# adapter.net
KiCad netlist of a schematic drawn in EAGLE
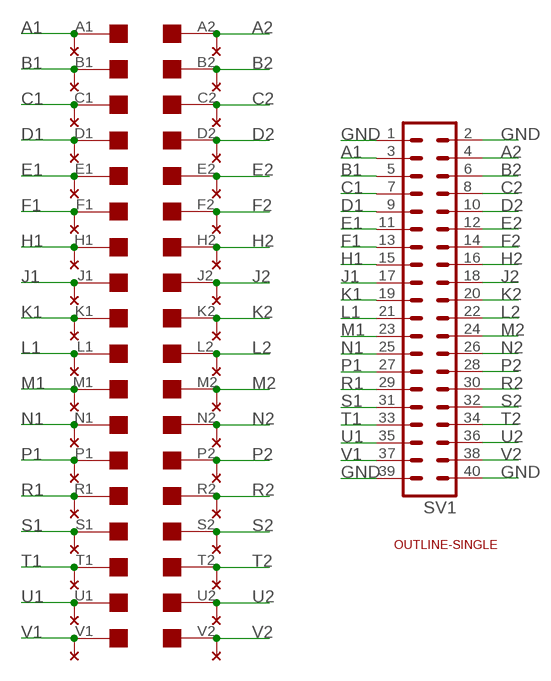
[diagram p0: schematic, sheet 1]

(export (version "E")
  (design (tool "Eeschema 10.0.6"))
  (components
    (comp (ref "EDGE1")
      (value "EDGE-2CONNECTOR")
      (footprint "eagle-import:EDGE-CON2")
      (libsource (lib "eagle-import") (part "EDGE-2CONNECTOR"))
    )
    (comp (ref "SV1")
      (value "MA20-2")
      (footprint "eagle-import:MA20-2")
      (libsource (lib "eagle-import") (part "MA20-2"))
    )
    (comp (ref "U$2")
      (value "OUTLINE-SINGLE")
      (footprint "eagle-import:SINGLE")
      (libsource (lib "eagle-import") (part "OUTLINE-SINGLE"))
    )
    (comp (ref "U$3")
      (value "THRU-HOLE2")
      (footprint "eagle-import:THRU-HOLEB")
      (libsource (lib "eagle-import") (part "THRU-HOLE2"))
    )
  )
  (nets
    (net (code "1") (name "/A1") (class "Default")
      (node (ref "EDGE1") (pin "A1") (pinfunction "1_A1") (pintype "bidirectional"))
      (node (ref "SV1") (pin "3") (pinfunction "3_3") (pintype "passive"))
      (node (ref "U$3") (pin "A1") (pinfunction "P$1_A1") (pintype "passive"))
    )
    (net (code "2") (name "/A2") (class "Default")
      (node (ref "EDGE1") (pin "A2") (pinfunction "1_A2") (pintype "bidirectional"))
      (node (ref "SV1") (pin "4") (pinfunction "4_4") (pintype "passive"))
      (node (ref "U$3") (pin "A2") (pinfunction "P$1_A2") (pintype "passive"))
    )
    (net (code "3") (name "/B1") (class "Default")
      (node (ref "EDGE1") (pin "B1") (pinfunction "1_B1") (pintype "bidirectional"))
      (node (ref "SV1") (pin "5") (pinfunction "5_5") (pintype "passive"))
      (node (ref "U$3") (pin "B1") (pinfunction "P$1_B1") (pintype "passive"))
    )
    (net (code "4") (name "/B2") (class "Default")
      (node (ref "EDGE1") (pin "B2") (pinfunction "1_B2") (pintype "bidirectional"))
      (node (ref "SV1") (pin "6") (pinfunction "6_6") (pintype "passive"))
      (node (ref "U$3") (pin "B2") (pinfunction "P$1_B2") (pintype "passive"))
    )
    (net (code "5") (name "/C1") (class "Default")
      (node (ref "EDGE1") (pin "C1") (pinfunction "1_C1") (pintype "bidirectional"))
      (node (ref "SV1") (pin "7") (pinfunction "7_7") (pintype "passive"))
      (node (ref "U$3") (pin "C1") (pinfunction "P$1_C1") (pintype "passive"))
    )
    (net (code "6") (name "/C2") (class "Default")
      (node (ref "EDGE1") (pin "C2") (pinfunction "1_C2") (pintype "bidirectional"))
      (node (ref "SV1") (pin "8") (pinfunction "8_8") (pintype "passive"))
      (node (ref "U$3") (pin "C2") (pinfunction "P$1_C2") (pintype "passive"))
    )
    (net (code "7") (name "/D1") (class "Default")
      (node (ref "EDGE1") (pin "D1") (pinfunction "1_D1") (pintype "bidirectional"))
      (node (ref "SV1") (pin "9") (pinfunction "9_9") (pintype "passive"))
      (node (ref "U$3") (pin "D1") (pinfunction "P$1_D1") (pintype "passive"))
    )
    (net (code "8") (name "/D2") (class "Default")
      (node (ref "EDGE1") (pin "D2") (pinfunction "1_D2") (pintype "bidirectional"))
      (node (ref "SV1") (pin "10") (pinfunction "10_10") (pintype "passive"))
      (node (ref "U$3") (pin "D2") (pinfunction "P$1_D2") (pintype "passive"))
    )
    (net (code "9") (name "/E1") (class "Default")
      (node (ref "EDGE1") (pin "E1") (pinfunction "1_E1") (pintype "bidirectional"))
      (node (ref "SV1") (pin "11") (pinfunction "11_11") (pintype "passive"))
      (node (ref "U$3") (pin "E1") (pinfunction "P$1_E1") (pintype "passive"))
    )
    (net (code "10") (name "/E2") (class "Default")
      (node (ref "EDGE1") (pin "E2") (pinfunction "1_E2") (pintype "bidirectional"))
      (node (ref "SV1") (pin "12") (pinfunction "12_12") (pintype "passive"))
      (node (ref "U$3") (pin "E2") (pinfunction "P$1_E2") (pintype "passive"))
    )
    (net (code "11") (name "/F1") (class "Default")
      (node (ref "EDGE1") (pin "F1") (pinfunction "1_F1") (pintype "bidirectional"))
      (node (ref "SV1") (pin "13") (pinfunction "13_13") (pintype "passive"))
      (node (ref "U$3") (pin "F1") (pinfunction "P$1_F1") (pintype "passive"))
    )
    (net (code "12") (name "/F2") (class "Default")
      (node (ref "EDGE1") (pin "F2") (pinfunction "1_F2") (pintype "bidirectional"))
      (node (ref "SV1") (pin "14") (pinfunction "14_14") (pintype "passive"))
      (node (ref "U$3") (pin "F2") (pinfunction "P$1_F2") (pintype "passive"))
    )
    (net (code "13") (name "/GND") (class "Default")
      (node (ref "SV1") (pin "1") (pinfunction "1_1") (pintype "passive"))
      (node (ref "SV1") (pin "2") (pinfunction "2_2") (pintype "passive"))
      (node (ref "SV1") (pin "39") (pinfunction "39_39") (pintype "passive"))
      (node (ref "SV1") (pin "40") (pinfunction "40_40") (pintype "passive"))
    )
    (net (code "14") (name "/H1") (class "Default")
      (node (ref "EDGE1") (pin "H1") (pinfunction "1_H1") (pintype "bidirectional"))
      (node (ref "SV1") (pin "15") (pinfunction "15_15") (pintype "passive"))
      (node (ref "U$3") (pin "H1") (pinfunction "P$1_H1") (pintype "passive"))
    )
    (net (code "15") (name "/H2") (class "Default")
      (node (ref "EDGE1") (pin "H2") (pinfunction "1_H2") (pintype "bidirectional"))
      (node (ref "SV1") (pin "16") (pinfunction "16_16") (pintype "passive"))
      (node (ref "U$3") (pin "H2") (pinfunction "P$1_H2") (pintype "passive"))
    )
    (net (code "16") (name "/J1") (class "Default")
      (node (ref "EDGE1") (pin "J1") (pinfunction "1_J1") (pintype "bidirectional"))
      (node (ref "SV1") (pin "17") (pinfunction "17_17") (pintype "passive"))
      (node (ref "U$3") (pin "J1") (pinfunction "P$1_J1") (pintype "passive"))
    )
    (net (code "17") (name "/J2") (class "Default")
      (node (ref "EDGE1") (pin "J2") (pinfunction "1_J2") (pintype "bidirectional"))
      (node (ref "SV1") (pin "18") (pinfunction "18_18") (pintype "passive"))
      (node (ref "U$3") (pin "J2") (pinfunction "P$1_J2") (pintype "passive"))
    )
    (net (code "18") (name "/K1") (class "Default")
      (node (ref "EDGE1") (pin "K1") (pinfunction "1_K1") (pintype "bidirectional"))
      (node (ref "SV1") (pin "19") (pinfunction "19_19") (pintype "passive"))
      (node (ref "U$3") (pin "K1") (pinfunction "P$1_K1") (pintype "passive"))
    )
    (net (code "19") (name "/K2") (class "Default")
      (node (ref "EDGE1") (pin "K2") (pinfunction "1_K2") (pintype "bidirectional"))
      (node (ref "SV1") (pin "20") (pinfunction "20_20") (pintype "passive"))
      (node (ref "U$3") (pin "K2") (pinfunction "P$1_K2") (pintype "passive"))
    )
    (net (code "20") (name "/L1") (class "Default")
      (node (ref "EDGE1") (pin "L1") (pinfunction "1_L1") (pintype "bidirectional"))
      (node (ref "SV1") (pin "21") (pinfunction "21_21") (pintype "passive"))
      (node (ref "U$3") (pin "L1") (pinfunction "P$1_L1") (pintype "passive"))
    )
    (net (code "21") (name "/L2") (class "Default")
      (node (ref "EDGE1") (pin "L2") (pinfunction "1_L2") (pintype "bidirectional"))
      (node (ref "SV1") (pin "22") (pinfunction "22_22") (pintype "passive"))
      (node (ref "U$3") (pin "L2") (pinfunction "P$1_L2") (pintype "passive"))
    )
    (net (code "22") (name "/M1") (class "Default")
      (node (ref "EDGE1") (pin "M1") (pinfunction "1_M1") (pintype "bidirectional"))
      (node (ref "SV1") (pin "23") (pinfunction "23_23") (pintype "passive"))
      (node (ref "U$3") (pin "M1") (pinfunction "P$1_M1") (pintype "passive"))
    )
    (net (code "23") (name "/M2") (class "Default")
      (node (ref "EDGE1") (pin "M2") (pinfunction "1_M2") (pintype "bidirectional"))
      (node (ref "SV1") (pin "24") (pinfunction "24_24") (pintype "passive"))
      (node (ref "U$3") (pin "M2") (pinfunction "P$1_M2") (pintype "passive"))
    )
    (net (code "24") (name "/N1") (class "Default")
      (node (ref "EDGE1") (pin "N1") (pinfunction "1_N1") (pintype "bidirectional"))
      (node (ref "SV1") (pin "25") (pinfunction "25_25") (pintype "passive"))
      (node (ref "U$3") (pin "N1") (pinfunction "P$1_N1") (pintype "passive"))
    )
    (net (code "25") (name "/N2") (class "Default")
      (node (ref "EDGE1") (pin "N2") (pinfunction "1_N2") (pintype "bidirectional"))
      (node (ref "SV1") (pin "26") (pinfunction "26_26") (pintype "passive"))
      (node (ref "U$3") (pin "N2") (pinfunction "P$1_N2") (pintype "passive"))
    )
    (net (code "26") (name "/P1") (class "Default")
      (node (ref "EDGE1") (pin "P1") (pinfunction "1_P1") (pintype "bidirectional"))
      (node (ref "SV1") (pin "27") (pinfunction "27_27") (pintype "passive"))
      (node (ref "U$3") (pin "P1") (pinfunction "P$1_P1") (pintype "passive"))
    )
    (net (code "27") (name "/P2") (class "Default")
      (node (ref "EDGE1") (pin "P2") (pinfunction "1_P2") (pintype "bidirectional"))
      (node (ref "SV1") (pin "28") (pinfunction "28_28") (pintype "passive"))
      (node (ref "U$3") (pin "P2") (pinfunction "P$1_P2") (pintype "passive"))
    )
    (net (code "28") (name "/R1") (class "Default")
      (node (ref "EDGE1") (pin "R1") (pinfunction "1_R1") (pintype "bidirectional"))
      (node (ref "SV1") (pin "29") (pinfunction "29_29") (pintype "passive"))
      (node (ref "U$3") (pin "R1") (pinfunction "P$1_R1") (pintype "passive"))
    )
    (net (code "29") (name "/R2") (class "Default")
      (node (ref "EDGE1") (pin "R2") (pinfunction "1_R2") (pintype "bidirectional"))
      (node (ref "SV1") (pin "30") (pinfunction "30_30") (pintype "passive"))
      (node (ref "U$3") (pin "R2") (pinfunction "P$1_R2") (pintype "passive"))
    )
    (net (code "30") (name "/S1") (class "Default")
      (node (ref "EDGE1") (pin "S1") (pinfunction "1_S1") (pintype "bidirectional"))
      (node (ref "SV1") (pin "31") (pinfunction "31_31") (pintype "passive"))
      (node (ref "U$3") (pin "S1") (pinfunction "P$1_S1") (pintype "passive"))
    )
    (net (code "31") (name "/S2") (class "Default")
      (node (ref "EDGE1") (pin "S2") (pinfunction "1_S2") (pintype "bidirectional"))
      (node (ref "SV1") (pin "32") (pinfunction "32_32") (pintype "passive"))
      (node (ref "U$3") (pin "S2") (pinfunction "P$1_S2") (pintype "passive"))
    )
    (net (code "32") (name "/T1") (class "Default")
      (node (ref "EDGE1") (pin "T1") (pinfunction "1_T1") (pintype "bidirectional"))
      (node (ref "SV1") (pin "33") (pinfunction "33_33") (pintype "passive"))
      (node (ref "U$3") (pin "T1") (pinfunction "P$1_T1") (pintype "passive"))
    )
    (net (code "33") (name "/T2") (class "Default")
      (node (ref "EDGE1") (pin "T2") (pinfunction "1_T2") (pintype "bidirectional"))
      (node (ref "SV1") (pin "34") (pinfunction "34_34") (pintype "passive"))
      (node (ref "U$3") (pin "T2") (pinfunction "P$1_T2") (pintype "passive"))
    )
    (net (code "34") (name "/U1") (class "Default")
      (node (ref "EDGE1") (pin "U1") (pinfunction "1_U1") (pintype "bidirectional"))
      (node (ref "SV1") (pin "35") (pinfunction "35_35") (pintype "passive"))
      (node (ref "U$3") (pin "U1") (pinfunction "P$1_U1") (pintype "passive"))
    )
    (net (code "35") (name "/U2") (class "Default")
      (node (ref "EDGE1") (pin "U2") (pinfunction "1_U2") (pintype "bidirectional"))
      (node (ref "SV1") (pin "36") (pinfunction "36_36") (pintype "passive"))
      (node (ref "U$3") (pin "U2") (pinfunction "P$1_U2") (pintype "passive"))
    )
    (net (code "36") (name "/V1") (class "Default")
      (node (ref "EDGE1") (pin "V1") (pinfunction "1_V1") (pintype "bidirectional"))
      (node (ref "SV1") (pin "37") (pinfunction "37_37") (pintype "passive"))
      (node (ref "U$3") (pin "V1") (pinfunction "P$1_V1") (pintype "passive"))
    )
    (net (code "37") (name "/V2") (class "Default")
      (node (ref "EDGE1") (pin "V2") (pinfunction "1_V2") (pintype "bidirectional"))
      (node (ref "SV1") (pin "38") (pinfunction "38_38") (pintype "passive"))
      (node (ref "U$3") (pin "V2") (pinfunction "P$1_V2") (pintype "passive"))
    )
  )
)
